# ottoesp-wrover.net
KiCad netlist of a schematic drawn in EAGLE
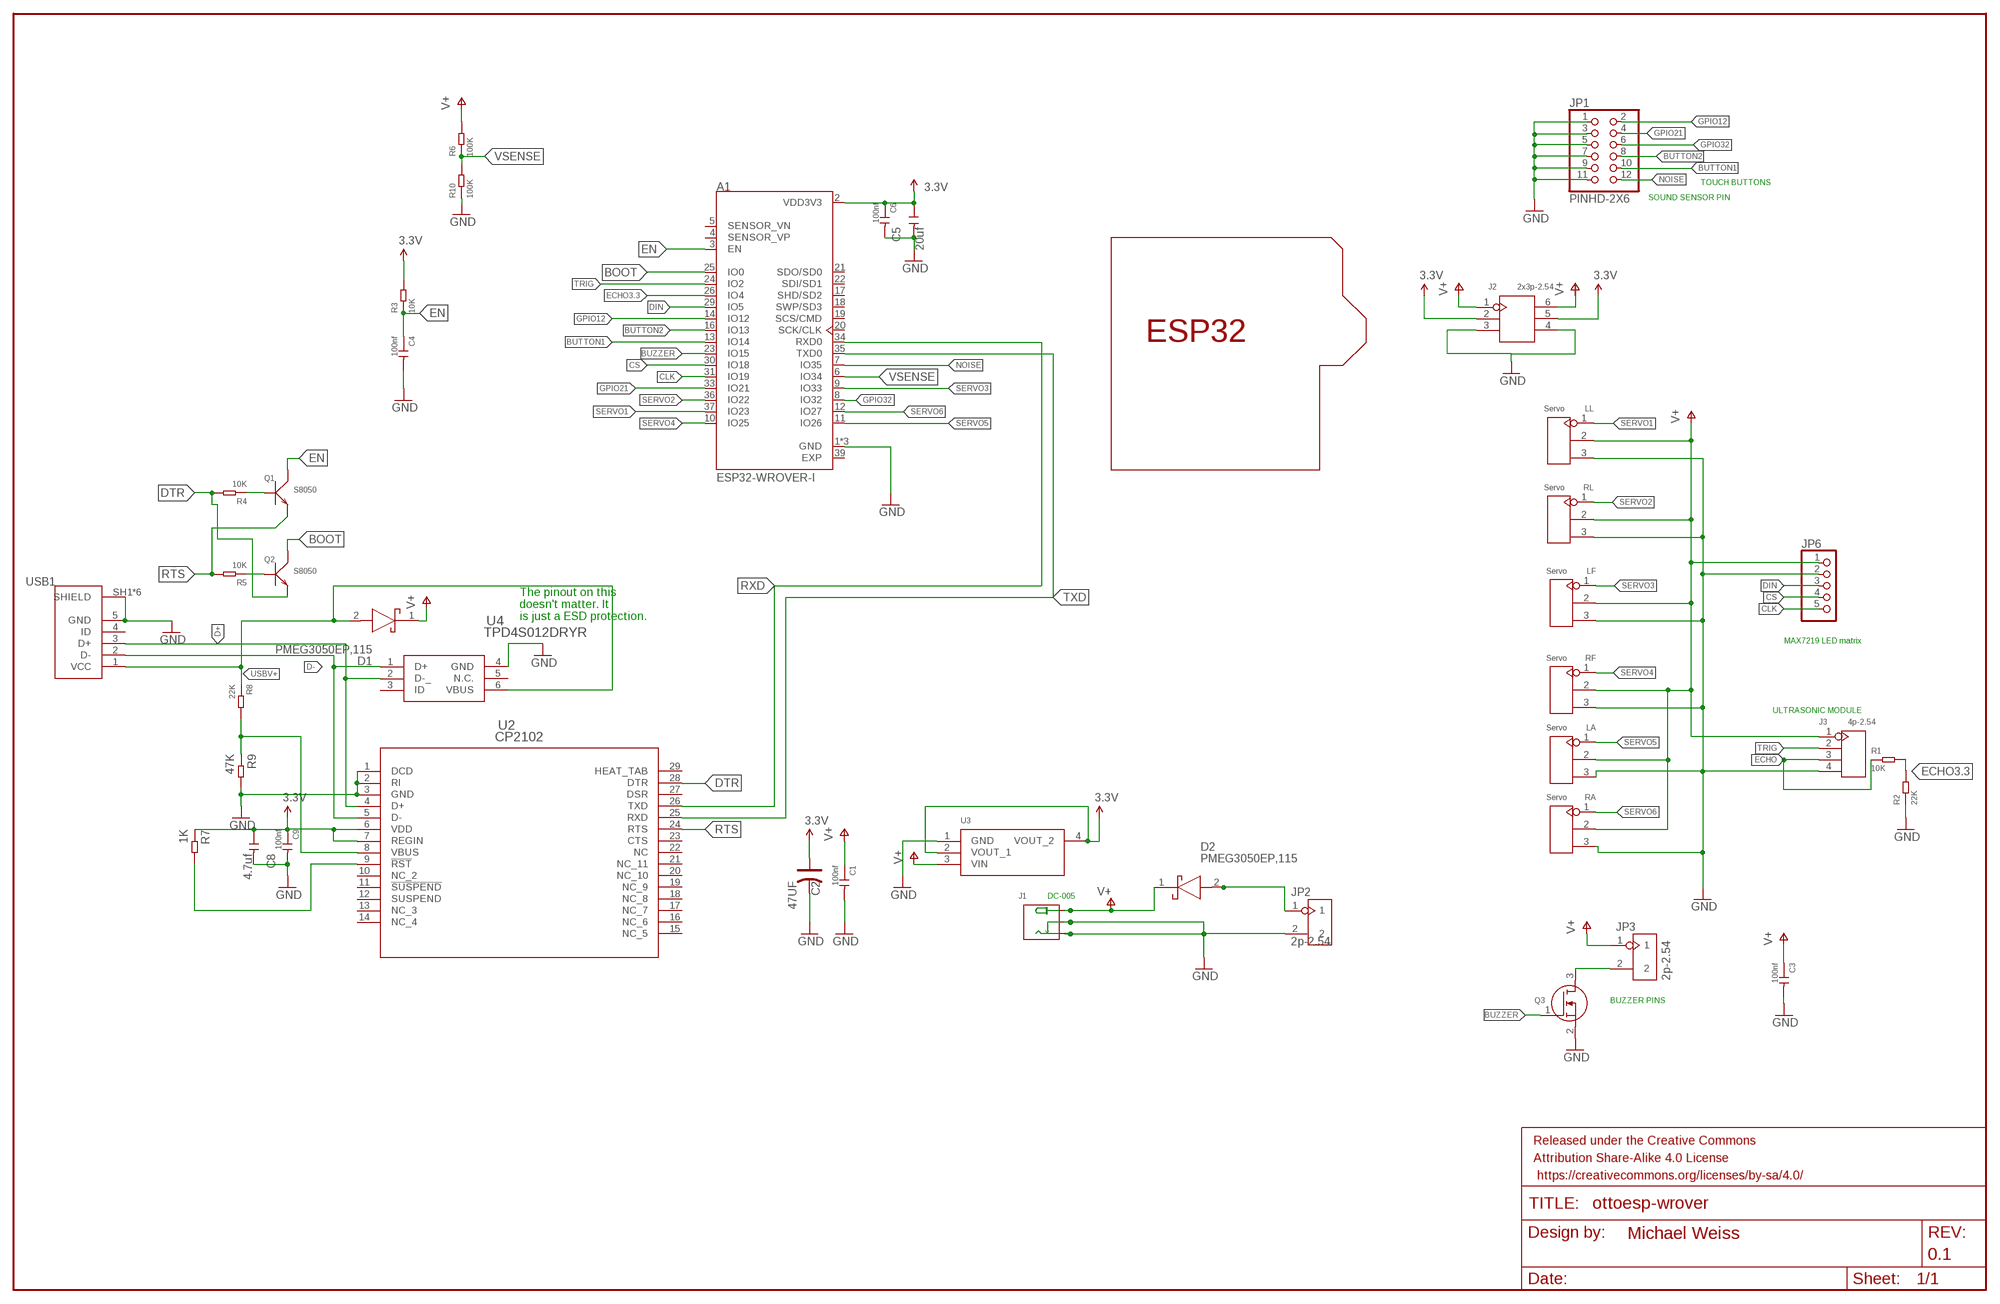
[diagram p0: schematic, sheet 1]

(export (version "E")
  (design (tool "Eeschema 10.0.6"))
  (components
    (comp (ref "A1")
      (value "ESP32-WROVER-I")
      (footprint "eagle-import:XCVR_ESP32-WROVER-I")
      (fields (field (name "MF") "Espressif Systems"))
      (libsource (lib "eagle-import") (part "ESP32-WROVER-I"))
    )
    (comp (ref "C1")
      (value "100nf")
      (footprint "eagle-import:C0805")
      (fields (field (name "MPN") "CC0805KRX7R9BB104"))
      (libsource (lib "eagle-import") (part "CERAMIC-100NF-50V-10%-X7R(0805)"))
    )
    (comp (ref "C2")
      (value "47UF")
      (footprint "eagle-import:ELECTRO-SMD-C-6MM")
      (fields (field (name "MPN") "CS1E470M-CRE54"))
      (libsource (lib "eagle-import") (part "ALUMINUM-SMD-47UF-25V(D6.3-H5.3MM)"))
    )
    (comp (ref "C3")
      (value "100nf")
      (footprint "eagle-import:C0805")
      (fields (field (name "MPN") "CC0805KRX7R9BB104"))
      (libsource (lib "eagle-import") (part "Seeed-Capacitor_CERAMIC-100NF-50V-10%-X7R(0805)"))
    )
    (comp (ref "C4")
      (value "100nf")
      (footprint "eagle-import:C0805")
      (fields (field (name "MPN") "CC0805KRX7R9BB104"))
      (libsource (lib "eagle-import") (part "CERAMIC-100NF-50V-10%-X7R(0805)"))
    )
    (comp (ref "C5")
      (value "20uf")
      (footprint "eagle-import:C1206")
      (libsource (lib "eagle-import") (part "CERAMIC-22UF-16V-10%-X7R(1206)"))
    )
    (comp (ref "C6")
      (value "100nf")
      (footprint "eagle-import:C0805")
      (fields (field (name "MPN") "CC0805KRX7R9BB104"))
      (libsource (lib "eagle-import") (part "CERAMIC-100NF-50V-10%-X7R(0805)"))
    )
    (comp (ref "C8")
      (value "4.7uf")
      (footprint "eagle-import:C0805")
      (fields (field (name "MPN") "CC0805KKX5R8BB475"))
      (libsource (lib "eagle-import") (part "CERAMIC-4.7UF-25V-10%-X5R(0805)"))
    )
    (comp (ref "C9")
      (value "100nf")
      (footprint "eagle-import:C0805")
      (fields (field (name "MPN") "CC0805KRX7R9BB104"))
      (libsource (lib "eagle-import") (part "CERAMIC-100NF-50V-10%-X7R(0805)"))
    )
    (comp (ref "D1")
      (value "PMEG3050EP,115")
      (footprint "eagle-import:PMEG3050EP115")
      (fields (field (name "MOUSER_PART_NUMBER") "771-PMEG3050EP115"))
      (libsource (lib "eagle-import") (part "PMEG3050EP,115"))
    )
    (comp (ref "D2")
      (value "PMEG3050EP,115")
      (footprint "eagle-import:PMEG3050EP115")
      (fields (field (name "MOUSER_PART_NUMBER") "771-PMEG3050EP115"))
      (libsource (lib "eagle-import") (part "PMEG3050EP,115"))
    )
    (comp (ref "FRAME1")
      (value "FRAME-LEDGERMISHAFARMS")
      (footprint "eagle-import:MISHAFARMS")
      (fields (field (name "DESIGNER") "Michael Weiss") (field (name "REV") "0.1"))
      (libsource (lib "eagle-import") (part "FRAME-LEDGERMISHAFARMS"))
    )
    (comp (ref "J1")
      (value "DC-005")
      (footprint "eagle-import:DCJ3P-14.2X11.0X9.0MM")
      (libsource (lib "eagle-import") (part "CONN-POWER-JACK-2.1MM(DC-005)"))
    )
    (comp (ref "J2")
      (value "2x3p-2.54")
      (footprint "eagle-import:H2X3-2.54")
      (fields (field (name "MPN") "P125-12A1BS116A1"))
      (libsource (lib "eagle-import") (part "DIP-BLACK-MALE-HEADER(2X3P-2.54）-2.54"))
    )
    (comp (ref "J3")
      (value "4p-2.54")
      (footprint "eagle-import:H4-2.54")
      (fields (field (name "MPN") "P125-1104A0BS116A1"))
      (libsource (lib "eagle-import") (part "DIP-BLACK-MALE-HEADER-VERT(4P-2.54)"))
    )
    (comp (ref "JP1")
      (value "PINHD-2X6")
      (footprint "eagle-import:2X06")
      (libsource (lib "eagle-import") (part "PINHD-2X6"))
    )
    (comp (ref "JP2")
      (value "2p-2.54")
      (footprint "eagle-import:H2-2.54")
      (fields (field (name "MPN") "P125-1102A0BS116A1"))
      (libsource (lib "eagle-import") (part "DIP-BLACK-MALE-HEADER-VERT(2P-2.54)"))
    )
    (comp (ref "JP3")
      (value "2p-2.54")
      (footprint "eagle-import:H2-2.54")
      (fields (field (name "MPN") "P125-1102A0BS116A1"))
      (libsource (lib "eagle-import") (part "DIP-BLACK-MALE-HEADER-VERT(2P-2.54)"))
    )
    (comp (ref "JP6")
      (value "PINHD-1X5")
      (footprint "eagle-import:1X05")
      (libsource (lib "eagle-import") (part "PINHD-1X5"))
    )
    (comp (ref "LA")
      (value "Servo")
      (footprint "eagle-import:H3-2.54")
      (libsource (lib "eagle-import") (part "DIP-BLACK-MALE-HEADER-VERT(3P-2.54)"))
    )
    (comp (ref "LF")
      (value "Servo")
      (footprint "eagle-import:H3-2.54")
      (libsource (lib "eagle-import") (part "DIP-BLACK-MALE-HEADER-VERT(3P-2.54)"))
    )
    (comp (ref "LL")
      (value "Servo")
      (footprint "eagle-import:H3-2.54")
      (libsource (lib "eagle-import") (part "DIP-BLACK-MALE-HEADER-VERT(3P-2.54)"))
    )
    (comp (ref "Q1")
      (value "S8050")
      (footprint "eagle-import:SOT-23")
      (libsource (lib "eagle-import") (part "SMD-TRANSISTORS-NPN-25V-500MW-S8050(SOT-23)"))
    )
    (comp (ref "Q2")
      (value "S8050")
      (footprint "eagle-import:SOT-23")
      (libsource (lib "eagle-import") (part "SMD-TRANSISTORS-NPN-25V-500MW-S8050(SOT-23)"))
    )
    (comp (ref "Q3")
      (value "CJ2302")
      (footprint "eagle-import:SOT95P230X110-3N")
      (fields
        (field (name "MANUFACTURER_PART_NUMBER") "2N7002NXAKR")
        (field (name "MOUSER_PART_NUMBER") "771-2N7002NXAKR")
      )
      (libsource (lib "eagle-import") (part "2N7002NXAKR"))
    )
    (comp (ref "R1")
      (value "10K")
      (footprint "eagle-import:R0805")
      (fields (field (name "MPN") "RC0805FR-0710KL"))
      (libsource (lib "eagle-import") (part "SMD-RES-10K-1%-1/8W(0805)"))
    )
    (comp (ref "R2")
      (value "22K")
      (footprint "eagle-import:R0805")
      (fields (field (name "MPN") "RC0805JR-071KL"))
      (libsource (lib "eagle-import") (part "SMD-RES-20K-5%-1/8W(0805)"))
    )
    (comp (ref "R3")
      (value "10K")
      (footprint "eagle-import:R0805")
      (fields (field (name "MPN") "RC0805FR-0710KL"))
      (libsource (lib "eagle-import") (part "SMD-RES-10K-1%-1/8W(0805)"))
    )
    (comp (ref "R4")
      (value "10K")
      (footprint "eagle-import:R0805")
      (fields (field (name "MPN") "RC0805FR-0710KL"))
      (libsource (lib "eagle-import") (part "SMD-RES-10K-1%-1/8W(0805)"))
    )
    (comp (ref "R5")
      (value "10K")
      (footprint "eagle-import:R0805")
      (fields (field (name "MPN") "RC0805FR-0710KL"))
      (libsource (lib "eagle-import") (part "SMD-RES-10K-1%-1/8W(0805)"))
    )
    (comp (ref "R6")
      (value "100K")
      (footprint "eagle-import:R0805")
      (fields (field (name "MPN") "RC0805JR-071KL"))
      (libsource (lib "eagle-import") (part "SMD-RES-100K-1%-1/8W(0805)"))
    )
    (comp (ref "R7")
      (value "1K")
      (footprint "eagle-import:R0805")
      (fields (field (name "MPN") "RC0805JR-071KL"))
      (libsource (lib "eagle-import") (part "SMD-RES-2K-1%-1/8W(0805)"))
    )
    (comp (ref "R8")
      (value "22K")
      (footprint "eagle-import:R0805")
      (fields (field (name "MPN") "RC0805JR-071KL"))
      (libsource (lib "eagle-import") (part "SMD-RES-22K-1%-1/8W(0805)"))
    )
    (comp (ref "R9")
      (value "47K")
      (footprint "eagle-import:R0805")
      (fields (field (name "MPN") "RC0805JR-071KL"))
      (libsource (lib "eagle-import") (part "SMD-RES-47R-1%-1/8W(0805)"))
    )
    (comp (ref "R10")
      (value "100K")
      (footprint "eagle-import:R0805")
      (fields (field (name "MPN") "RC0805JR-071KL"))
      (libsource (lib "eagle-import") (part "SMD-RES-100K-1%-1/8W(0805)"))
    )
    (comp (ref "RA")
      (value "Servo")
      (footprint "eagle-import:H3-2.54")
      (libsource (lib "eagle-import") (part "DIP-BLACK-MALE-HEADER-VERT(3P-2.54)"))
    )
    (comp (ref "RF")
      (value "Servo")
      (footprint "eagle-import:H3-2.54")
      (libsource (lib "eagle-import") (part "DIP-BLACK-MALE-HEADER-VERT(3P-2.54)"))
    )
    (comp (ref "RL")
      (value "Servo")
      (footprint "eagle-import:H3-2.54")
      (libsource (lib "eagle-import") (part "DIP-BLACK-MALE-HEADER-VERT(3P-2.54)"))
    )
    (comp (ref "U$2")
      (value "ESP32_SHIELDSMALL")
      (footprint "eagle-import:ESP32_ARDUINOSHIELDSMALL")
      (libsource (lib "eagle-import") (part "ESP32_SHIELDSMALL"))
    )
    (comp (ref "U2")
      (value "CP2102")
      (footprint "eagle-import:QFN28N5X5-0P5P")
      (libsource (lib "eagle-import") (part "CP2102"))
    )
    (comp (ref "U3")
      (value "CJA1117B-3.3-SOT89")
      (footprint "eagle-import:SOT230P700X180-4N")
      (fields
        (field (name "MANUFACTURER_PART_NUMBER") "AP2114H-3.3TRG1")
        (field (name "MOUSER_PART_NUMBER") "621-AP2114H-3.3TRG1")
      )
      (libsource (lib "eagle-import") (part "AP2114H-3.3TRG1"))
    )
    (comp (ref "U4")
      (value "TPD4S012DRYR")
      (footprint "eagle-import:TPD4S012DRYR")
      (fields (field (name "MOUSER_PART_NUMBER") "595-TPD4S012DRYR"))
      (libsource (lib "eagle-import") (part "TPD4S012DRYR"))
    )
    (comp (ref "USB1")
      (value "ZX62-B-5PA")
      (footprint "eagle-import:HRS_ZX62-B-5PA(33)")
      (fields (field (name "MF") "Hirose") (field (name "MP") "ZX62-B-5PA_33_"))
      (libsource (lib "eagle-import") (part "ZX62-B-5PA(33)"))
    )
  )
  (nets
    (net (code "1") (name "/EXP") (class "Default")
      (node (ref "A1") (pin "39") (pinfunction "EXP_39") (pintype "power_in"))
    )
    (net (code "2") (name "3.3V") (class "Default")
      (node (ref "A1") (pin "2") (pinfunction "VDD3V3_2") (pintype "power_in"))
      (node (ref "C2") (pin "+") (pinfunction "+_+") (pintype "passive"))
      (node (ref "C5") (pin "1") (pinfunction "1_1") (pintype "passive"))
      (node (ref "C6") (pin "1") (pinfunction "1_1") (pintype "passive"))
      (node (ref "C8") (pin "1") (pinfunction "1_1") (pintype "passive"))
      (node (ref "C9") (pin "1") (pinfunction "1_1") (pintype "passive"))
      (node (ref "J2") (pin "2") (pinfunction "2_2") (pintype "bidirectional"))
      (node (ref "J2") (pin "5") (pinfunction "5_5") (pintype "bidirectional"))
      (node (ref "R3") (pin "2") (pinfunction "2_2") (pintype "passive"))
      (node (ref "R7") (pin "1") (pinfunction "1_1") (pintype "passive"))
      (node (ref "U2") (pin "6") (pinfunction "VDD_6") (pintype "passive"))
      (node (ref "U2") (pin "7") (pinfunction "REGIN_7") (pintype "passive"))
      (node (ref "U3") (pin "2") (pinfunction "VOUT_1_2") (pintype "bidirectional"))
      (node (ref "U3") (pin "4") (pinfunction "VOUT_2_4") (pintype "bidirectional"))
    )
    (net (code "3") (name "BOOT") (class "Default")
      (node (ref "A1") (pin "25") (pinfunction "IO0_25") (pintype "bidirectional"))
      (node (ref "Q2") (pin "3") (pinfunction "C_3") (pintype "passive"))
    )
    (net (code "4") (name "BUTTON1") (class "Default")
      (node (ref "A1") (pin "13") (pinfunction "IO14_13") (pintype "bidirectional"))
      (node (ref "JP1") (pin "10") (pinfunction "10_10") (pintype "passive"))
    )
    (net (code "5") (name "BUTTON2") (class "Default")
      (node (ref "A1") (pin "16") (pinfunction "IO13_16") (pintype "bidirectional"))
      (node (ref "JP1") (pin "8") (pinfunction "8_8") (pintype "passive"))
    )
    (net (code "6") (name "BUZZER") (class "Default")
      (node (ref "A1") (pin "23") (pinfunction "IO15_23") (pintype "bidirectional"))
      (node (ref "Q3") (pin "1") (pinfunction "G_1") (pintype "bidirectional"))
    )
    (net (code "7") (name "CLK") (class "Default")
      (node (ref "A1") (pin "31") (pinfunction "IO19_31") (pintype "bidirectional"))
      (node (ref "JP6") (pin "5") (pinfunction "5_5") (pintype "passive"))
    )
    (net (code "8") (name "CS") (class "Default")
      (node (ref "A1") (pin "30") (pinfunction "IO18_30") (pintype "bidirectional"))
      (node (ref "JP6") (pin "4") (pinfunction "4_4") (pintype "passive"))
    )
    (net (code "9") (name "D+") (class "Default")
      (node (ref "U2") (pin "4") (pinfunction "D+_4") (pintype "passive"))
      (node (ref "U4") (pin "2") (pinfunction "D-__2") (pintype "bidirectional"))
      (node (ref "USB1") (pin "3") (pinfunction "D+_3") (pintype "passive"))
    )
    (net (code "10") (name "D-") (class "Default")
      (node (ref "U2") (pin "5") (pinfunction "D-_5") (pintype "passive"))
      (node (ref "U4") (pin "1") (pinfunction "D+_1") (pintype "bidirectional"))
      (node (ref "USB1") (pin "2") (pinfunction "D-_2") (pintype "passive"))
    )
    (net (code "11") (name "DIN") (class "Default")
      (node (ref "A1") (pin "29") (pinfunction "IO5_29") (pintype "bidirectional"))
      (node (ref "JP6") (pin "3") (pinfunction "3_3") (pintype "passive"))
    )
    (net (code "12") (name "DTR") (class "Default")
      (node (ref "Q2") (pin "2") (pinfunction "E_2") (pintype "passive"))
      (node (ref "R4") (pin "2") (pinfunction "2_2") (pintype "passive"))
      (node (ref "U2") (pin "28") (pinfunction "DTR_28") (pintype "passive"))
    )
    (net (code "13") (name "ECHO") (class "Default")
      (node (ref "J3") (pin "3") (pinfunction "P$3_3") (pintype "bidirectional"))
      (node (ref "R1") (pin "1") (pinfunction "1_1") (pintype "passive"))
    )
    (net (code "14") (name "ECHO3.3") (class "Default")
      (node (ref "A1") (pin "26") (pinfunction "IO4_26") (pintype "bidirectional"))
      (node (ref "R1") (pin "2") (pinfunction "2_2") (pintype "passive"))
      (node (ref "R2") (pin "2") (pinfunction "2_2") (pintype "passive"))
    )
    (net (code "15") (name "EN") (class "Default")
      (node (ref "A1") (pin "3") (pinfunction "EN_3") (pintype "input"))
      (node (ref "C4") (pin "1") (pinfunction "1_1") (pintype "passive"))
      (node (ref "Q1") (pin "3") (pinfunction "C_3") (pintype "passive"))
      (node (ref "R3") (pin "1") (pinfunction "1_1") (pintype "passive"))
    )
    (net (code "16") (name "GND") (class "Default")
      (node (ref "A1") (pin "1") (pinfunction "GND_1") (pintype "power_in"))
      (node (ref "A1") (pin "15") (pinfunction "GND_15") (pintype "power_in"))
      (node (ref "A1") (pin "38") (pinfunction "GND_38") (pintype "power_in"))
      (node (ref "C1") (pin "2") (pinfunction "2_2") (pintype "passive"))
      (node (ref "C2") (pin "-") (pinfunction "-_-") (pintype "passive"))
      (node (ref "C3") (pin "2") (pinfunction "2_2") (pintype "passive"))
      (node (ref "C4") (pin "2") (pinfunction "2_2") (pintype "passive"))
      (node (ref "C5") (pin "2") (pinfunction "2_2") (pintype "passive"))
      (node (ref "C6") (pin "2") (pinfunction "2_2") (pintype "passive"))
      (node (ref "C8") (pin "2") (pinfunction "2_2") (pintype "passive"))
      (node (ref "C9") (pin "2") (pinfunction "2_2") (pintype "passive"))
      (node (ref "J1") (pin "-1") (pinfunction "-_-1") (pintype "bidirectional"))
      (node (ref "J1") (pin "-2") (pinfunction "CDN_-2") (pintype "bidirectional"))
      (node (ref "J2") (pin "3") (pinfunction "3_3") (pintype "bidirectional"))
      (node (ref "J2") (pin "4") (pinfunction "4_4") (pintype "bidirectional"))
      (node (ref "J3") (pin "4") (pinfunction "P$4_4") (pintype "bidirectional"))
      (node (ref "JP1") (pin "1") (pinfunction "1_1") (pintype "passive"))
      (node (ref "JP1") (pin "11") (pinfunction "11_11") (pintype "passive"))
      (node (ref "JP1") (pin "3") (pinfunction "3_3") (pintype "passive"))
      (node (ref "JP1") (pin "5") (pinfunction "5_5") (pintype "passive"))
      (node (ref "JP1") (pin "7") (pinfunction "7_7") (pintype "passive"))
      (node (ref "JP1") (pin "9") (pinfunction "9_9") (pintype "passive"))
      (node (ref "JP2") (pin "2") (pinfunction "2_2") (pintype "bidirectional"))
      (node (ref "JP6") (pin "2") (pinfunction "2_2") (pintype "passive"))
      (node (ref "LA") (pin "3") (pinfunction "P$3_3") (pintype "bidirectional"))
      (node (ref "LF") (pin "3") (pinfunction "P$3_3") (pintype "bidirectional"))
      (node (ref "LL") (pin "3") (pinfunction "P$3_3") (pintype "bidirectional"))
      (node (ref "Q3") (pin "2") (pinfunction "S_2") (pintype "bidirectional"))
      (node (ref "R10") (pin "1") (pinfunction "1_1") (pintype "passive"))
      (node (ref "R2") (pin "1") (pinfunction "1_1") (pintype "passive"))
      (node (ref "R9") (pin "2") (pinfunction "2_2") (pintype "passive"))
      (node (ref "RA") (pin "3") (pinfunction "P$3_3") (pintype "bidirectional"))
      (node (ref "RF") (pin "3") (pinfunction "P$3_3") (pintype "bidirectional"))
      (node (ref "RL") (pin "3") (pinfunction "P$3_3") (pintype "bidirectional"))
      (node (ref "U2") (pin "1") (pinfunction "DCD_1") (pintype "passive"))
      (node (ref "U2") (pin "2") (pinfunction "RI_2") (pintype "passive"))
      (node (ref "U2") (pin "3") (pinfunction "GND_3") (pintype "passive"))
      (node (ref "U3") (pin "1") (pinfunction "GND_1") (pintype "bidirectional"))
      (node (ref "U4") (pin "4") (pinfunction "GND_4") (pintype "bidirectional"))
      (node (ref "USB1") (pin "5") (pinfunction "GND_5") (pintype "passive"))
      (node (ref "USB1") (pin "SH1") (pinfunction "SHIELD_SH1") (pintype "passive"))
      (node (ref "USB1") (pin "SH2") (pinfunction "SHIELD_SH2") (pintype "passive"))
      (node (ref "USB1") (pin "SH3") (pinfunction "SHIELD_SH3") (pintype "passive"))
      (node (ref "USB1") (pin "SH4") (pinfunction "SHIELD_SH4") (pintype "passive"))
      (node (ref "USB1") (pin "SH5") (pinfunction "SHIELD_SH5") (pintype "passive"))
      (node (ref "USB1") (pin "SH6") (pinfunction "SHIELD_SH6") (pintype "passive"))
    )
    (net (code "17") (name "GPIO12") (class "Default")
      (node (ref "A1") (pin "14") (pinfunction "IO12_14") (pintype "bidirectional"))
      (node (ref "JP1") (pin "2") (pinfunction "2_2") (pintype "passive"))
    )
    (net (code "18") (name "GPIO21") (class "Default")
      (node (ref "A1") (pin "33") (pinfunction "IO21_33") (pintype "bidirectional"))
      (node (ref "JP1") (pin "4") (pinfunction "4_4") (pintype "passive"))
    )
    (net (code "19") (name "GPIO32") (class "Default")
      (node (ref "A1") (pin "8") (pinfunction "IO32_8") (pintype "bidirectional"))
      (node (ref "JP1") (pin "6") (pinfunction "6_6") (pintype "passive"))
    )
    (net (code "20") (name "NOISE") (class "Default")
      (node (ref "A1") (pin "7") (pinfunction "IO35_7") (pintype "input"))
      (node (ref "JP1") (pin "12") (pinfunction "12_12") (pintype "passive"))
    )
    (net (code "21") (name "Net-(D2-A)") (class "Default")
      (node (ref "D2") (pin "2") (pinfunction "A_2") (pintype "bidirectional"))
      (node (ref "JP2") (pin "1") (pinfunction "1_1") (pintype "bidirectional"))
    )
    (net (code "22") (name "Net-(Q1-B)") (class "Default")
      (node (ref "Q1") (pin "1") (pinfunction "B_1") (pintype "passive"))
      (node (ref "R4") (pin "1") (pinfunction "1_1") (pintype "passive"))
    )
    (net (code "23") (name "Net-(Q2-B)") (class "Default")
      (node (ref "Q2") (pin "1") (pinfunction "B_1") (pintype "passive"))
      (node (ref "R5") (pin "1") (pinfunction "1_1") (pintype "passive"))
    )
    (net (code "24") (name "Net-(Q3-D)") (class "Default")
      (node (ref "JP3") (pin "2") (pinfunction "2_2") (pintype "bidirectional"))
      (node (ref "Q3") (pin "3") (pinfunction "D_3") (pintype "bidirectional"))
    )
    (net (code "25") (name "Net-(U2-VBUS)") (class "Default")
      (node (ref "R8") (pin "2") (pinfunction "2_2") (pintype "passive"))
      (node (ref "R9") (pin "1") (pinfunction "1_1") (pintype "passive"))
      (node (ref "U2") (pin "8") (pinfunction "VBUS_8") (pintype "passive"))
    )
    (net (code "26") (name "Net-(U2-~{RST})") (class "Default")
      (node (ref "R7") (pin "2") (pinfunction "2_2") (pintype "passive"))
      (node (ref "U2") (pin "9") (pinfunction "~{RST}_9") (pintype "passive"))
    )
    (net (code "27") (name "RTS") (class "Default")
      (node (ref "Q1") (pin "2") (pinfunction "E_2") (pintype "passive"))
      (node (ref "R5") (pin "2") (pinfunction "2_2") (pintype "passive"))
      (node (ref "U2") (pin "24") (pinfunction "RTS_24") (pintype "passive"))
    )
    (net (code "28") (name "RXD") (class "Default")
      (node (ref "A1") (pin "34") (pinfunction "RXD0_34") (pintype "bidirectional"))
      (node (ref "U2") (pin "26") (pinfunction "TXD_26") (pintype "passive"))
    )
    (net (code "29") (name "SERVO1") (class "Default")
      (node (ref "A1") (pin "37") (pinfunction "IO23_37") (pintype "bidirectional"))
      (node (ref "LL") (pin "1") (pinfunction "P$1_1") (pintype "bidirectional"))
    )
    (net (code "30") (name "SERVO2") (class "Default")
      (node (ref "A1") (pin "36") (pinfunction "IO22_36") (pintype "bidirectional"))
      (node (ref "RL") (pin "1") (pinfunction "P$1_1") (pintype "bidirectional"))
    )
    (net (code "31") (name "SERVO3") (class "Default")
      (node (ref "A1") (pin "9") (pinfunction "IO33_9") (pintype "bidirectional"))
      (node (ref "LF") (pin "1") (pinfunction "P$1_1") (pintype "bidirectional"))
    )
    (net (code "32") (name "SERVO4") (class "Default")
      (node (ref "A1") (pin "10") (pinfunction "IO25_10") (pintype "bidirectional"))
      (node (ref "RF") (pin "1") (pinfunction "P$1_1") (pintype "bidirectional"))
    )
    (net (code "33") (name "SERVO5") (class "Default")
      (node (ref "A1") (pin "11") (pinfunction "IO26_11") (pintype "bidirectional"))
      (node (ref "LA") (pin "1") (pinfunction "P$1_1") (pintype "bidirectional"))
    )
    (net (code "34") (name "SERVO6") (class "Default")
      (node (ref "A1") (pin "12") (pinfunction "IO27_12") (pintype "bidirectional"))
      (node (ref "RA") (pin "1") (pinfunction "P$1_1") (pintype "bidirectional"))
    )
    (net (code "35") (name "TRIG") (class "Default")
      (node (ref "A1") (pin "24") (pinfunction "IO2_24") (pintype "bidirectional"))
      (node (ref "J3") (pin "2") (pinfunction "P$2_2") (pintype "bidirectional"))
    )
    (net (code "36") (name "TXD") (class "Default")
      (node (ref "A1") (pin "35") (pinfunction "TXD0_35") (pintype "bidirectional"))
      (node (ref "U2") (pin "25") (pinfunction "RXD_25") (pintype "passive"))
    )
    (net (code "37") (name "USBV+") (class "Default")
      (node (ref "D1") (pin "2") (pinfunction "A_2") (pintype "bidirectional"))
      (node (ref "R8") (pin "1") (pinfunction "1_1") (pintype "passive"))
      (node (ref "U4") (pin "6") (pinfunction "VBUS_6") (pintype "bidirectional"))
      (node (ref "USB1") (pin "1") (pinfunction "VCC_1") (pintype "passive"))
    )
    (net (code "38") (name "V+") (class "Default")
      (node (ref "C1") (pin "1") (pinfunction "1_1") (pintype "passive"))
      (node (ref "C3") (pin "1") (pinfunction "1_1") (pintype "passive"))
      (node (ref "D1") (pin "1") (pinfunction "K_1") (pintype "bidirectional"))
      (node (ref "D2") (pin "1") (pinfunction "K_1") (pintype "bidirectional"))
      (node (ref "J1") (pin "+") (pinfunction "+_+") (pintype "bidirectional"))
      (node (ref "J2") (pin "1") (pinfunction "1_1") (pintype "bidirectional"))
      (node (ref "J2") (pin "6") (pinfunction "6_6") (pintype "bidirectional"))
      (node (ref "J3") (pin "1") (pinfunction "P$1_1") (pintype "bidirectional"))
      (node (ref "JP3") (pin "1") (pinfunction "1_1") (pintype "bidirectional"))
      (node (ref "JP6") (pin "1") (pinfunction "1_1") (pintype "passive"))
      (node (ref "LA") (pin "2") (pinfunction "P$2_2") (pintype "bidirectional"))
      (node (ref "LF") (pin "2") (pinfunction "P$2_2") (pintype "bidirectional"))
      (node (ref "LL") (pin "2") (pinfunction "P$2_2") (pintype "bidirectional"))
      (node (ref "R6") (pin "2") (pinfunction "2_2") (pintype "passive"))
      (node (ref "RA") (pin "2") (pinfunction "P$2_2") (pintype "bidirectional"))
      (node (ref "RF") (pin "2") (pinfunction "P$2_2") (pintype "bidirectional"))
      (node (ref "RL") (pin "2") (pinfunction "P$2_2") (pintype "bidirectional"))
      (node (ref "U3") (pin "3") (pinfunction "VIN_3") (pintype "bidirectional"))
    )
    (net (code "39") (name "VSENSE") (class "Default")
      (node (ref "A1") (pin "6") (pinfunction "IO34_6") (pintype "input"))
      (node (ref "R10") (pin "2") (pinfunction "2_2") (pintype "passive"))
      (node (ref "R6") (pin "1") (pinfunction "1_1") (pintype "passive"))
    )
    (net (code "40") (name "unconnected-(A1-SCK{slash}CLK-Pad20)") (class "Default")
      (node (ref "A1") (pin "20") (pinfunction "SCK/CLK_20") (pintype "bidirectional"))
    )
    (net (code "41") (name "unconnected-(A1-SCS{slash}CMD-Pad19)") (class "Default")
      (node (ref "A1") (pin "19") (pinfunction "SCS/CMD_19") (pintype "bidirectional"))
    )
    (net (code "42") (name "unconnected-(A1-SDI{slash}SD1-Pad22)") (class "Default")
      (node (ref "A1") (pin "22") (pinfunction "SDI/SD1_22") (pintype "bidirectional"))
    )
    (net (code "43") (name "unconnected-(A1-SDO{slash}SD0-Pad21)") (class "Default")
      (node (ref "A1") (pin "21") (pinfunction "SDO/SD0_21") (pintype "bidirectional"))
    )
    (net (code "44") (name "unconnected-(A1-SENSOR_VN-Pad5)") (class "Default")
      (node (ref "A1") (pin "5") (pinfunction "SENSOR_VN_5") (pintype "input"))
    )
    (net (code "45") (name "unconnected-(A1-SENSOR_VP-Pad4)") (class "Default")
      (node (ref "A1") (pin "4") (pinfunction "SENSOR_VP_4") (pintype "input"))
    )
    (net (code "46") (name "unconnected-(A1-SHD{slash}SD2-Pad17)") (class "Default")
      (node (ref "A1") (pin "17") (pinfunction "SHD/SD2_17") (pintype "bidirectional"))
    )
    (net (code "47") (name "unconnected-(A1-SWP{slash}SD3-Pad18)") (class "Default")
      (node (ref "A1") (pin "18") (pinfunction "SWP/SD3_18") (pintype "bidirectional"))
    )
    (net (code "48") (name "unconnected-(U2-CTS-Pad23)") (class "Default")
      (node (ref "U2") (pin "23") (pinfunction "CTS_23") (pintype "passive"))
    )
    (net (code "49") (name "unconnected-(U2-DSR-Pad27)") (class "Default")
      (node (ref "U2") (pin "27") (pinfunction "DSR_27") (pintype "passive"))
    )
    (net (code "50") (name "unconnected-(U2-HEAT_TAB-Pad29)") (class "Default")
      (node (ref "U2") (pin "29") (pinfunction "HEAT_TAB_29") (pintype "passive"))
    )
    (net (code "51") (name "unconnected-(U2-NC-Pad22)") (class "Default")
      (node (ref "U2") (pin "22") (pinfunction "NC_22") (pintype "passive"))
    )
    (net (code "52") (name "unconnected-(U2-NC_2-Pad10)") (class "Default")
      (node (ref "U2") (pin "10") (pinfunction "NC_2_10") (pintype "passive"))
    )
    (net (code "53") (name "unconnected-(U2-NC_3-Pad13)") (class "Default")
      (node (ref "U2") (pin "13") (pinfunction "NC_3_13") (pintype "passive"))
    )
    (net (code "54") (name "unconnected-(U2-NC_4-Pad14)") (class "Default")
      (node (ref "U2") (pin "14") (pinfunction "NC_4_14") (pintype "passive"))
    )
    (net (code "55") (name "unconnected-(U2-NC_5-Pad15)") (class "Default")
      (node (ref "U2") (pin "15") (pinfunction "NC_5_15") (pintype "passive"))
    )
    (net (code "56") (name "unconnected-(U2-NC_6-Pad16)") (class "Default")
      (node (ref "U2") (pin "16") (pinfunction "NC_6_16") (pintype "passive"))
    )
    (net (code "57") (name "unconnected-(U2-NC_7-Pad17)") (class "Default")
      (node (ref "U2") (pin "17") (pinfunction "NC_7_17") (pintype "passive"))
    )
    (net (code "58") (name "unconnected-(U2-NC_8-Pad18)") (class "Default")
      (node (ref "U2") (pin "18") (pinfunction "NC_8_18") (pintype "passive"))
    )
    (net (code "59") (name "unconnected-(U2-NC_9-Pad19)") (class "Default")
      (node (ref "U2") (pin "19") (pinfunction "NC_9_19") (pintype "passive"))
    )
    (net (code "60") (name "unconnected-(U2-NC_10-Pad20)") (class "Default")
      (node (ref "U2") (pin "20") (pinfunction "NC_10_20") (pintype "passive"))
    )
    (net (code "61") (name "unconnected-(U2-NC_11-Pad21)") (class "Default")
      (node (ref "U2") (pin "21") (pinfunction "NC_11_21") (pintype "passive"))
    )
    (net (code "62") (name "unconnected-(U2-SUSPEND-Pad12)") (class "Default")
      (node (ref "U2") (pin "12") (pinfunction "SUSPEND_12") (pintype "passive"))
    )
    (net (code "63") (name "unconnected-(U2-~{SUSPEND}-Pad11)") (class "Default")
      (node (ref "U2") (pin "11") (pinfunction "~{SUSPEND}_11") (pintype "passive"))
    )
    (net (code "64") (name "unconnected-(U4-ID-Pad3)") (class "Default")
      (node (ref "U4") (pin "3") (pinfunction "ID_3") (pintype "bidirectional"))
    )
    (net (code "65") (name "unconnected-(U4-N.C.-Pad5)") (class "Default")
      (node (ref "U4") (pin "5") (pinfunction "N.C._5") (pintype "no_connect"))
    )
    (net (code "66") (name "unconnected-(USB1-ID-Pad4)") (class "Default")
      (node (ref "USB1") (pin "4") (pinfunction "ID_4") (pintype "passive"))
    )
  )
)
